# Button.net
KiCad netlist of a schematic drawn in Altium Designer
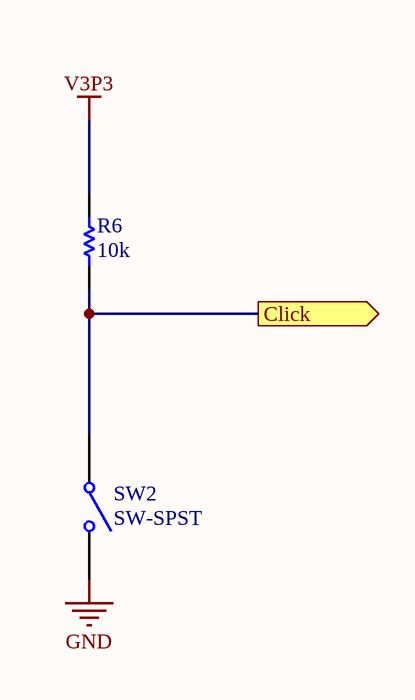
[diagram p0: Button.SchDoc]

(export (version "E")
  (design (tool "Eeschema 10.0.6"))
  (components
    (comp (ref "R6")
      (value "10k")
      (footprint "RES 0603")
      (description "Resistor")
      (libsource (lib "Miscellaneous Devices") (part "Res1"))
    )
    (comp (ref "SW2")
      (value "SW-SPST")
      (footprint "SWITCH")
      (description "Single-Pole, Single-Throw Switch")
      (libsource (lib "Miscellaneous Devices") (part "SW-SPST"))
    )
  )
  (nets
    (net (code "1") (name "/Click") (class "Default")
      (node (ref "R6") (pin "1") (pinfunction "1_1") (pintype "passive"))
      (node (ref "SW2") (pin "1") (pinfunction "COMMON_1") (pintype "passive"))
    )
    (net (code "2") (name "GND") (class "Default")
      (node (ref "SW2") (pin "2") (pinfunction "NO_2") (pintype "passive"))
    )
    (net (code "3") (name "V3P3") (class "Default")
      (node (ref "R6") (pin "2") (pinfunction "2_2") (pintype "passive"))
    )
  )
)
